# HEATER.net
KiCad netlist of a schematic drawn in Altium Designer
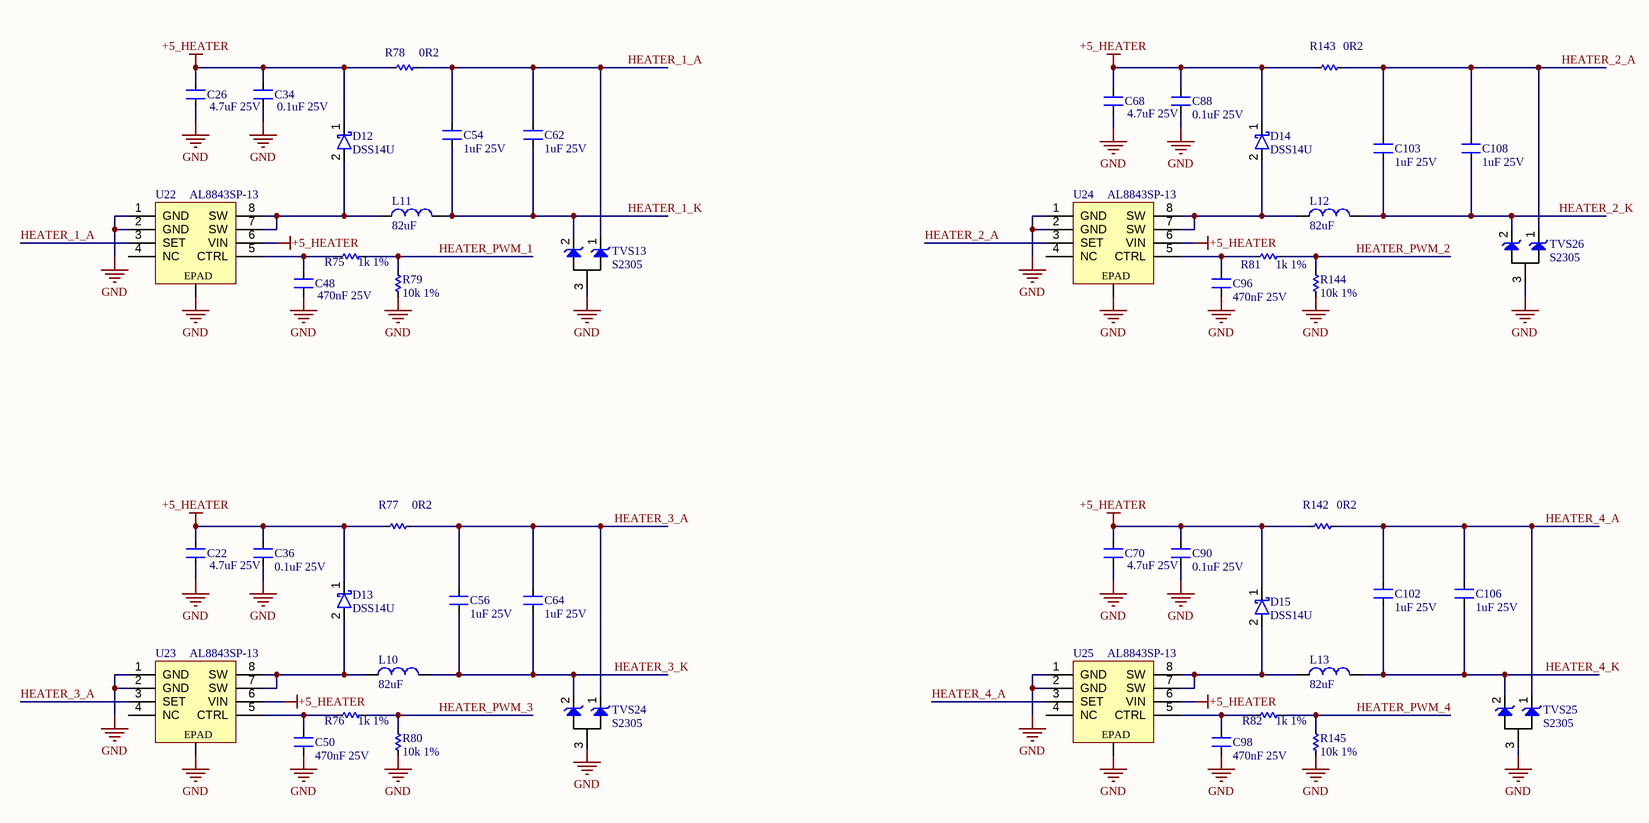
[diagram p0: HEATER.SchDoc]

(export (version "E")
  (design (tool "Eeschema 10.0.6"))
  (components
    (comp (ref "C22")
      (value "4.7uF 25V")
      (footprint "CN-SMD-0603")
      (libsource (lib "Sang_library") (part "Capacitors"))
    )
    (comp (ref "C26")
      (value "4.7uF 25V")
      (footprint "CN-SMD-0603")
      (libsource (lib "Sang_library") (part "Capacitors"))
    )
    (comp (ref "C34")
      (value "0.1uF 25V")
      (footprint "CN-SMD-0603")
      (libsource (lib "Sang_library") (part "Capacitors"))
    )
    (comp (ref "C36")
      (value "0.1uF 25V")
      (footprint "CN-SMD-0603")
      (libsource (lib "Sang_library") (part "Capacitors"))
    )
    (comp (ref "C48")
      (value "470nF 25V")
      (footprint "CN-SMD-0603")
      (libsource (lib "Sang_library") (part "Capacitors"))
    )
    (comp (ref "C50")
      (value "470nF 25V")
      (footprint "CN-SMD-0603")
      (libsource (lib "Sang_library") (part "Capacitors"))
    )
    (comp (ref "C54")
      (value "1uF 25V")
      (footprint "CN-SMD-0603")
      (libsource (lib "Sang_library") (part "Capacitors"))
    )
    (comp (ref "C56")
      (value "1uF 25V")
      (footprint "CN-SMD-0603")
      (libsource (lib "Sang_library") (part "Capacitors"))
    )
    (comp (ref "C62")
      (value "1uF 25V")
      (footprint "CN-SMD-0603")
      (libsource (lib "Sang_library") (part "Capacitors"))
    )
    (comp (ref "C64")
      (value "1uF 25V")
      (footprint "CN-SMD-0603")
      (libsource (lib "Sang_library") (part "Capacitors"))
    )
    (comp (ref "C68")
      (value "4.7uF 25V")
      (footprint "CN-SMD-0603")
      (libsource (lib "Sang_library") (part "Capacitors"))
    )
    (comp (ref "C70")
      (value "4.7uF 25V")
      (footprint "CN-SMD-0603")
      (libsource (lib "Sang_library") (part "Capacitors"))
    )
    (comp (ref "C88")
      (value "0.1uF 25V")
      (footprint "CN-SMD-0603")
      (libsource (lib "Sang_library") (part "Capacitors"))
    )
    (comp (ref "C90")
      (value "0.1uF 25V")
      (footprint "CN-SMD-0603")
      (libsource (lib "Sang_library") (part "Capacitors"))
    )
    (comp (ref "C96")
      (value "470nF 25V")
      (footprint "CN-SMD-0603")
      (libsource (lib "Sang_library") (part "Capacitors"))
    )
    (comp (ref "C98")
      (value "470nF 25V")
      (footprint "CN-SMD-0603")
      (libsource (lib "Sang_library") (part "Capacitors"))
    )
    (comp (ref "C102")
      (value "1uF 25V")
      (footprint "CN-SMD-0603")
      (libsource (lib "Sang_library") (part "Capacitors"))
    )
    (comp (ref "C103")
      (value "1uF 25V")
      (footprint "CN-SMD-0603")
      (libsource (lib "Sang_library") (part "Capacitors"))
    )
    (comp (ref "C106")
      (value "1uF 25V")
      (footprint "CN-SMD-0603")
      (libsource (lib "Sang_library") (part "Capacitors"))
    )
    (comp (ref "C108")
      (value "1uF 25V")
      (footprint "CN-SMD-0603")
      (libsource (lib "Sang_library") (part "Capacitors"))
    )
    (comp (ref "D12") (value "DSS14U") (footprint "sod-123") (libsource (lib "Sang_library") (part "DSS14U")))
    (comp (ref "D13") (value "DSS14U") (footprint "sod-123") (libsource (lib "Sang_library") (part "DSS14U")))
    (comp (ref "D14") (value "DSS14U") (footprint "sod-123") (libsource (lib "Sang_library") (part "DSS14U")))
    (comp (ref "D15") (value "DSS14U") (footprint "sod-123") (libsource (lib "Sang_library") (part "DSS14U")))
    (comp (ref "L10")
      (value "82uF")
      (footprint "L-SMD-M-4.8x4.8x2.8mm")
      (description "FIXED IND 82UH 2.25A 160MOHM SMD\r\nPN: 744770182")
      (fields
        (field (name "PARTNO") "78477010")
        (field (name "MANUFACTURER") "Wurth Elektronik")
        (field (name "CREATED BY") "Baojun Chen")
      )
      (libsource (lib "Sang_library") (part "L-SMD-1"))
    )
    (comp (ref "L11")
      (value "82uF")
      (footprint "L-SMD-M-4.8x4.8x2.8mm")
      (description "FIXED IND 82UH 2.25A 160MOHM SMD\r\nPN: 744770182")
      (fields
        (field (name "PARTNO") "78477010")
        (field (name "MANUFACTURER") "Wurth Elektronik")
        (field (name "CREATED BY") "Baojun Chen")
      )
      (libsource (lib "Sang_library") (part "L-SMD-1"))
    )
    (comp (ref "L12")
      (value "82uF")
      (footprint "L-SMD-M-4.8x4.8x2.8mm")
      (description "FIXED IND 82UH 2.25A 160MOHM SMD\r\nPN: 744770182")
      (fields
        (field (name "PARTNO") "78477010")
        (field (name "MANUFACTURER") "Wurth Elektronik")
        (field (name "CREATED BY") "Baojun Chen")
      )
      (libsource (lib "Sang_library") (part "L-SMD-1"))
    )
    (comp (ref "L13")
      (value "82uF")
      (footprint "L-SMD-M-4.8x4.8x2.8mm")
      (description "FIXED IND 82UH 2.25A 160MOHM SMD\r\nPN: 744770182")
      (fields
        (field (name "PARTNO") "78477010")
        (field (name "MANUFACTURER") "Wurth Elektronik")
        (field (name "CREATED BY") "Baojun Chen")
      )
      (libsource (lib "Sang_library") (part "L-SMD-1"))
    )
    (comp (ref "R75")
      (value "1k 1%")
      (footprint "RES-SMD-0603")
      (description "SMD")
      (fields
        (field (name "MANUFACTURER") "Generic Components")
        (field (name "PUBLISHER") "Altium Hobart Technology Centre")
      )
      (libsource (lib "Sang_library") (part "Res SMD"))
    )
    (comp (ref "R76")
      (value "1k 1%")
      (footprint "RES-SMD-0603")
      (description "SMD")
      (fields
        (field (name "MANUFACTURER") "Generic Components")
        (field (name "PUBLISHER") "Altium Hobart Technology Centre")
      )
      (libsource (lib "Sang_library") (part "Res SMD"))
    )
    (comp (ref "R77")
      (value "0R2")
      (footprint "RES-SMD-1206")
      (description "RES 0.1 OHM 1% 1W 1206\r\nPN: PE1206FRF470R1L")
      (fields
        (field (name "MANUFACTURER") "Generic Components")
        (field (name "PUBLISHER") "Altium Hobart Technology Centre")
      )
      (libsource (lib "Library") (part "Res-SMD"))
    )
    (comp (ref "R78")
      (value "0R2")
      (footprint "RES-SMD-1206")
      (description "RES 0.1 OHM 1% 1W 1206\r\nPN: PE1206FRF470R1L")
      (fields
        (field (name "MANUFACTURER") "Generic Components")
        (field (name "PUBLISHER") "Altium Hobart Technology Centre")
      )
      (libsource (lib "Library") (part "Res-SMD"))
    )
    (comp (ref "R79")
      (value "10k 1%")
      (footprint "RES-SMD-0603")
      (description "SMD")
      (fields
        (field (name "MANUFACTURER") "Generic Components")
        (field (name "PUBLISHER") "Altium Hobart Technology Centre")
      )
      (libsource (lib "Sang_library") (part "Res SMD"))
    )
    (comp (ref "R80")
      (value "10k 1%")
      (footprint "RES-SMD-0603")
      (description "SMD")
      (fields
        (field (name "MANUFACTURER") "Generic Components")
        (field (name "PUBLISHER") "Altium Hobart Technology Centre")
      )
      (libsource (lib "Sang_library") (part "Res SMD"))
    )
    (comp (ref "R81")
      (value "1k 1%")
      (footprint "RES-SMD-0603")
      (description "SMD")
      (fields
        (field (name "MANUFACTURER") "Generic Components")
        (field (name "PUBLISHER") "Altium Hobart Technology Centre")
      )
      (libsource (lib "Sang_library") (part "Res SMD"))
    )
    (comp (ref "R82")
      (value "1k 1%")
      (footprint "RES-SMD-0603")
      (description "SMD")
      (fields
        (field (name "MANUFACTURER") "Generic Components")
        (field (name "PUBLISHER") "Altium Hobart Technology Centre")
      )
      (libsource (lib "Sang_library") (part "Res SMD"))
    )
    (comp (ref "R142")
      (value "0R2")
      (footprint "RES-SMD-1206")
      (description "RES 0.1 OHM 1% 1W 1206\r\nPN: PE1206FRF470R1L")
      (fields
        (field (name "MANUFACTURER") "Generic Components")
        (field (name "PUBLISHER") "Altium Hobart Technology Centre")
      )
      (libsource (lib "Library") (part "Res-SMD"))
    )
    (comp (ref "R143")
      (value "0R2")
      (footprint "RES-SMD-1206")
      (description "RES 0.1 OHM 1% 1W 1206\r\nPN: PE1206FRF470R1L")
      (fields
        (field (name "MANUFACTURER") "Generic Components")
        (field (name "PUBLISHER") "Altium Hobart Technology Centre")
      )
      (libsource (lib "Library") (part "Res-SMD"))
    )
    (comp (ref "R144")
      (value "10k 1%")
      (footprint "RES-SMD-0603")
      (description "SMD")
      (fields
        (field (name "MANUFACTURER") "Generic Components")
        (field (name "PUBLISHER") "Altium Hobart Technology Centre")
      )
      (libsource (lib "Sang_library") (part "Res SMD"))
    )
    (comp (ref "R145")
      (value "10k 1%")
      (footprint "RES-SMD-0603")
      (description "SMD")
      (fields
        (field (name "MANUFACTURER") "Generic Components")
        (field (name "PUBLISHER") "Altium Hobart Technology Centre")
      )
      (libsource (lib "Sang_library") (part "Res SMD"))
    )
    (comp (ref "TVS13")
      (value "S2305")
      (footprint "sot23-12_3")
      (description "TVS DIODE 5VWM 10.8VC SOT23")
      (libsource (lib "Sang_library") (part "S2305"))
    )
    (comp (ref "TVS24")
      (value "S2305")
      (footprint "sot23-12_3")
      (description "TVS DIODE 5VWM 10.8VC SOT23")
      (libsource (lib "Sang_library") (part "S2305"))
    )
    (comp (ref "TVS25")
      (value "S2305")
      (footprint "sot23-12_3")
      (description "TVS DIODE 5VWM 10.8VC SOT23")
      (libsource (lib "Sang_library") (part "S2305"))
    )
    (comp (ref "TVS26")
      (value "S2305")
      (footprint "sot23-12_3")
      (description "TVS DIODE 5VWM 10.8VC SOT23")
      (libsource (lib "Sang_library") (part "S2305"))
    )
    (comp (ref "U22")
      (value "AL8843SP-13")
      (footprint "SO8_EPAD")
      (description "IC LED DRIVER RGLTR PWM 3A 8SO")
      (libsource (lib "Sang_library") (part "AL8843SP-13"))
    )
    (comp (ref "U23")
      (value "AL8843SP-13")
      (footprint "SO8_EPAD")
      (description "IC LED DRIVER RGLTR PWM 3A 8SO")
      (libsource (lib "Sang_library") (part "AL8843SP-13"))
    )
    (comp (ref "U24")
      (value "AL8843SP-13")
      (footprint "SO8_EPAD")
      (description "IC LED DRIVER RGLTR PWM 3A 8SO")
      (libsource (lib "Sang_library") (part "AL8843SP-13"))
    )
    (comp (ref "U25")
      (value "AL8843SP-13")
      (footprint "SO8_EPAD")
      (description "IC LED DRIVER RGLTR PWM 3A 8SO")
      (libsource (lib "Sang_library") (part "AL8843SP-13"))
    )
  )
  (nets
    (net (code "1") (name "+5_HEATER") (class "Default")
      (node (ref "C22") (pin "2") (pinfunction "2_2") (pintype "passive"))
      (node (ref "C26") (pin "2") (pinfunction "2_2") (pintype "passive"))
      (node (ref "C34") (pin "2") (pinfunction "2_2") (pintype "passive"))
      (node (ref "C36") (pin "2") (pinfunction "2_2") (pintype "passive"))
      (node (ref "C68") (pin "2") (pinfunction "2_2") (pintype "passive"))
      (node (ref "C70") (pin "2") (pinfunction "2_2") (pintype "passive"))
      (node (ref "C88") (pin "2") (pinfunction "2_2") (pintype "passive"))
      (node (ref "C90") (pin "2") (pinfunction "2_2") (pintype "passive"))
      (node (ref "D12") (pin "1") (pinfunction "1_1") (pintype "passive"))
      (node (ref "D13") (pin "1") (pinfunction "1_1") (pintype "passive"))
      (node (ref "D14") (pin "1") (pinfunction "1_1") (pintype "passive"))
      (node (ref "D15") (pin "1") (pinfunction "1_1") (pintype "passive"))
      (node (ref "R142") (pin "2") (pinfunction "2_2") (pintype "passive"))
      (node (ref "R143") (pin "2") (pinfunction "2_2") (pintype "passive"))
      (node (ref "R77") (pin "2") (pinfunction "2_2") (pintype "passive"))
      (node (ref "R78") (pin "2") (pinfunction "2_2") (pintype "passive"))
      (node (ref "U22") (pin "6") (pinfunction "VIN_6") (pintype "passive"))
      (node (ref "U23") (pin "6") (pinfunction "VIN_6") (pintype "passive"))
      (node (ref "U24") (pin "6") (pinfunction "VIN_6") (pintype "passive"))
      (node (ref "U25") (pin "6") (pinfunction "VIN_6") (pintype "passive"))
    )
    (net (code "2") (name "/HEATER_1_A") (class "Default")
      (node (ref "C54") (pin "2") (pinfunction "2_2") (pintype "passive"))
      (node (ref "C62") (pin "2") (pinfunction "2_2") (pintype "passive"))
      (node (ref "R78") (pin "1") (pinfunction "1_1") (pintype "passive"))
      (node (ref "TVS13") (pin "1") (pinfunction "1_1") (pintype "passive"))
      (node (ref "U22") (pin "3") (pinfunction "SET_3") (pintype "passive"))
    )
    (net (code "3") (name "/HEATER_1_K") (class "Default")
      (node (ref "C54") (pin "1") (pinfunction "1_1") (pintype "passive"))
      (node (ref "C62") (pin "1") (pinfunction "1_1") (pintype "passive"))
      (node (ref "L11") (pin "2") (pinfunction "2_2") (pintype "passive"))
      (node (ref "TVS13") (pin "2") (pinfunction "2_2") (pintype "passive"))
    )
    (net (code "4") (name "/HEATER_2_A") (class "Default")
      (node (ref "C103") (pin "2") (pinfunction "2_2") (pintype "passive"))
      (node (ref "C108") (pin "2") (pinfunction "2_2") (pintype "passive"))
      (node (ref "R143") (pin "1") (pinfunction "1_1") (pintype "passive"))
      (node (ref "TVS26") (pin "1") (pinfunction "1_1") (pintype "passive"))
      (node (ref "U24") (pin "3") (pinfunction "SET_3") (pintype "passive"))
    )
    (net (code "5") (name "/HEATER_2_K") (class "Default")
      (node (ref "C103") (pin "1") (pinfunction "1_1") (pintype "passive"))
      (node (ref "C108") (pin "1") (pinfunction "1_1") (pintype "passive"))
      (node (ref "L12") (pin "2") (pinfunction "2_2") (pintype "passive"))
      (node (ref "TVS26") (pin "2") (pinfunction "2_2") (pintype "passive"))
    )
    (net (code "6") (name "/HEATER_3_A") (class "Default")
      (node (ref "C56") (pin "2") (pinfunction "2_2") (pintype "passive"))
      (node (ref "C64") (pin "2") (pinfunction "2_2") (pintype "passive"))
      (node (ref "R77") (pin "1") (pinfunction "1_1") (pintype "passive"))
      (node (ref "TVS24") (pin "1") (pinfunction "1_1") (pintype "passive"))
      (node (ref "U23") (pin "3") (pinfunction "SET_3") (pintype "passive"))
    )
    (net (code "7") (name "/HEATER_3_K") (class "Default")
      (node (ref "C56") (pin "1") (pinfunction "1_1") (pintype "passive"))
      (node (ref "C64") (pin "1") (pinfunction "1_1") (pintype "passive"))
      (node (ref "L10") (pin "2") (pinfunction "2_2") (pintype "passive"))
      (node (ref "TVS24") (pin "2") (pinfunction "2_2") (pintype "passive"))
    )
    (net (code "8") (name "/HEATER_4_A") (class "Default")
      (node (ref "C102") (pin "2") (pinfunction "2_2") (pintype "passive"))
      (node (ref "C106") (pin "2") (pinfunction "2_2") (pintype "passive"))
      (node (ref "R142") (pin "1") (pinfunction "1_1") (pintype "passive"))
      (node (ref "TVS25") (pin "1") (pinfunction "1_1") (pintype "passive"))
      (node (ref "U25") (pin "3") (pinfunction "SET_3") (pintype "passive"))
    )
    (net (code "9") (name "/HEATER_4_K") (class "Default")
      (node (ref "C102") (pin "1") (pinfunction "1_1") (pintype "passive"))
      (node (ref "C106") (pin "1") (pinfunction "1_1") (pintype "passive"))
      (node (ref "L13") (pin "2") (pinfunction "2_2") (pintype "passive"))
      (node (ref "TVS25") (pin "2") (pinfunction "2_2") (pintype "passive"))
    )
    (net (code "10") (name "/HEATER_PWM_1") (class "Default")
      (node (ref "R75") (pin "2") (pinfunction "2_2") (pintype "passive"))
      (node (ref "R79") (pin "2") (pinfunction "2_2") (pintype "passive"))
    )
    (net (code "11") (name "/HEATER_PWM_2") (class "Default")
      (node (ref "R144") (pin "2") (pinfunction "2_2") (pintype "passive"))
      (node (ref "R81") (pin "2") (pinfunction "2_2") (pintype "passive"))
    )
    (net (code "12") (name "/HEATER_PWM_3") (class "Default")
      (node (ref "R76") (pin "2") (pinfunction "2_2") (pintype "passive"))
      (node (ref "R80") (pin "2") (pinfunction "2_2") (pintype "passive"))
    )
    (net (code "13") (name "/HEATER_PWM_4") (class "Default")
      (node (ref "R145") (pin "2") (pinfunction "2_2") (pintype "passive"))
      (node (ref "R82") (pin "2") (pinfunction "2_2") (pintype "passive"))
    )
    (net (code "14") (name "GND") (class "Default")
      (node (ref "C22") (pin "1") (pinfunction "1_1") (pintype "passive"))
      (node (ref "C26") (pin "1") (pinfunction "1_1") (pintype "passive"))
      (node (ref "C34") (pin "1") (pinfunction "1_1") (pintype "passive"))
      (node (ref "C36") (pin "1") (pinfunction "1_1") (pintype "passive"))
      (node (ref "C48") (pin "1") (pinfunction "1_1") (pintype "passive"))
      (node (ref "C50") (pin "1") (pinfunction "1_1") (pintype "passive"))
      (node (ref "C68") (pin "1") (pinfunction "1_1") (pintype "passive"))
      (node (ref "C70") (pin "1") (pinfunction "1_1") (pintype "passive"))
      (node (ref "C88") (pin "1") (pinfunction "1_1") (pintype "passive"))
      (node (ref "C90") (pin "1") (pinfunction "1_1") (pintype "passive"))
      (node (ref "C96") (pin "1") (pinfunction "1_1") (pintype "passive"))
      (node (ref "C98") (pin "1") (pinfunction "1_1") (pintype "passive"))
      (node (ref "R144") (pin "1") (pinfunction "1_1") (pintype "passive"))
      (node (ref "R145") (pin "1") (pinfunction "1_1") (pintype "passive"))
      (node (ref "R79") (pin "1") (pinfunction "1_1") (pintype "passive"))
      (node (ref "R80") (pin "1") (pinfunction "1_1") (pintype "passive"))
      (node (ref "TVS13") (pin "3") (pinfunction "3_3") (pintype "passive"))
      (node (ref "TVS24") (pin "3") (pinfunction "3_3") (pintype "passive"))
      (node (ref "TVS25") (pin "3") (pinfunction "3_3") (pintype "passive"))
      (node (ref "TVS26") (pin "3") (pinfunction "3_3") (pintype "passive"))
      (node (ref "U22") (pin "1") (pinfunction "GND_1") (pintype "passive"))
      (node (ref "U22") (pin "2") (pinfunction "GND_2") (pintype "passive"))
      (node (ref "U22") (pin "EPAD") (pinfunction "EPAD_EPAD") (pintype "passive"))
      (node (ref "U23") (pin "1") (pinfunction "GND_1") (pintype "passive"))
      (node (ref "U23") (pin "2") (pinfunction "GND_2") (pintype "passive"))
      (node (ref "U23") (pin "EPAD") (pinfunction "EPAD_EPAD") (pintype "passive"))
      (node (ref "U24") (pin "1") (pinfunction "GND_1") (pintype "passive"))
      (node (ref "U24") (pin "2") (pinfunction "GND_2") (pintype "passive"))
      (node (ref "U24") (pin "EPAD") (pinfunction "EPAD_EPAD") (pintype "passive"))
      (node (ref "U25") (pin "1") (pinfunction "GND_1") (pintype "passive"))
      (node (ref "U25") (pin "2") (pinfunction "GND_2") (pintype "passive"))
      (node (ref "U25") (pin "EPAD") (pinfunction "EPAD_EPAD") (pintype "passive"))
    )
    (net (code "15") (name "Net-(D12-Pad2)") (class "Default")
      (node (ref "D12") (pin "2") (pinfunction "2_2") (pintype "passive"))
      (node (ref "L11") (pin "1") (pinfunction "1_1") (pintype "passive"))
      (node (ref "U22") (pin "7") (pinfunction "SW_7") (pintype "passive"))
      (node (ref "U22") (pin "8") (pinfunction "SW_8") (pintype "passive"))
    )
    (net (code "16") (name "Net-(D13-Pad2)") (class "Default")
      (node (ref "D13") (pin "2") (pinfunction "2_2") (pintype "passive"))
      (node (ref "L10") (pin "1") (pinfunction "1_1") (pintype "passive"))
      (node (ref "U23") (pin "7") (pinfunction "SW_7") (pintype "passive"))
      (node (ref "U23") (pin "8") (pinfunction "SW_8") (pintype "passive"))
    )
    (net (code "17") (name "Net-(D14-Pad2)") (class "Default")
      (node (ref "D14") (pin "2") (pinfunction "2_2") (pintype "passive"))
      (node (ref "L12") (pin "1") (pinfunction "1_1") (pintype "passive"))
      (node (ref "U24") (pin "7") (pinfunction "SW_7") (pintype "passive"))
      (node (ref "U24") (pin "8") (pinfunction "SW_8") (pintype "passive"))
    )
    (net (code "18") (name "Net-(D15-Pad2)") (class "Default")
      (node (ref "D15") (pin "2") (pinfunction "2_2") (pintype "passive"))
      (node (ref "L13") (pin "1") (pinfunction "1_1") (pintype "passive"))
      (node (ref "U25") (pin "7") (pinfunction "SW_7") (pintype "passive"))
      (node (ref "U25") (pin "8") (pinfunction "SW_8") (pintype "passive"))
    )
    (net (code "19") (name "Net-(U22-CTRL)") (class "Default")
      (node (ref "C48") (pin "2") (pinfunction "2_2") (pintype "passive"))
      (node (ref "R75") (pin "1") (pinfunction "1_1") (pintype "passive"))
      (node (ref "U22") (pin "5") (pinfunction "CTRL_5") (pintype "passive"))
    )
    (net (code "20") (name "Net-(U23-CTRL)") (class "Default")
      (node (ref "C50") (pin "2") (pinfunction "2_2") (pintype "passive"))
      (node (ref "R76") (pin "1") (pinfunction "1_1") (pintype "passive"))
      (node (ref "U23") (pin "5") (pinfunction "CTRL_5") (pintype "passive"))
    )
    (net (code "21") (name "Net-(U24-CTRL)") (class "Default")
      (node (ref "C96") (pin "2") (pinfunction "2_2") (pintype "passive"))
      (node (ref "R81") (pin "1") (pinfunction "1_1") (pintype "passive"))
      (node (ref "U24") (pin "5") (pinfunction "CTRL_5") (pintype "passive"))
    )
    (net (code "22") (name "Net-(U25-CTRL)") (class "Default")
      (node (ref "C98") (pin "2") (pinfunction "2_2") (pintype "passive"))
      (node (ref "R82") (pin "1") (pinfunction "1_1") (pintype "passive"))
      (node (ref "U25") (pin "5") (pinfunction "CTRL_5") (pintype "passive"))
    )
    (net (code "23") (name "unconnected-(U22-NC-Pad4)") (class "Default")
      (node (ref "U22") (pin "4") (pinfunction "NC_4") (pintype "passive"))
    )
    (net (code "24") (name "unconnected-(U23-NC-Pad4)") (class "Default")
      (node (ref "U23") (pin "4") (pinfunction "NC_4") (pintype "passive"))
    )
    (net (code "25") (name "unconnected-(U24-NC-Pad4)") (class "Default")
      (node (ref "U24") (pin "4") (pinfunction "NC_4") (pintype "passive"))
    )
    (net (code "26") (name "unconnected-(U25-NC-Pad4)") (class "Default")
      (node (ref "U25") (pin "4") (pinfunction "NC_4") (pintype "passive"))
    )
  )
)
